# shield.net
KiCad netlist of a schematic drawn in EAGLE
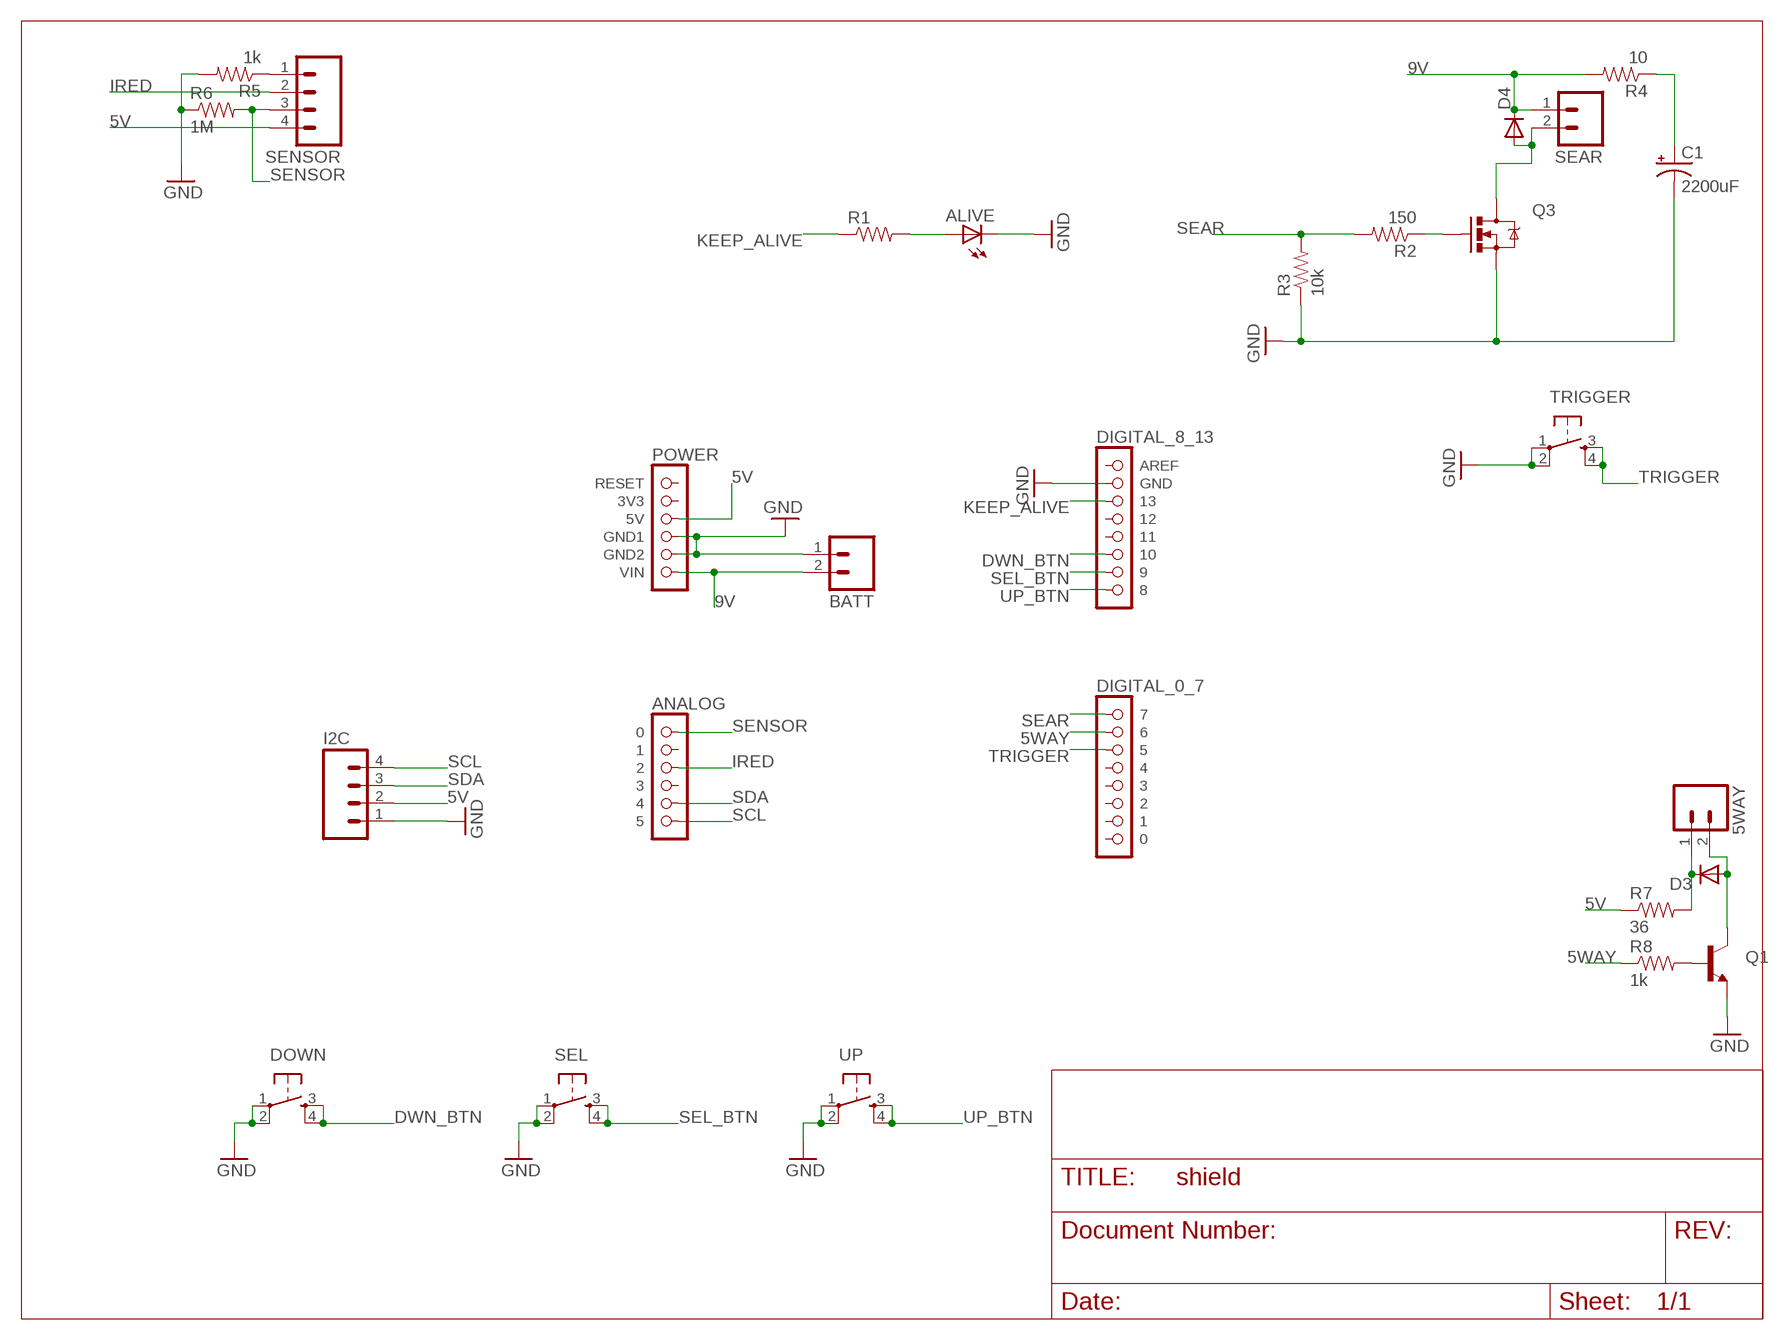
[diagram p0: schematic, sheet 1]

(export (version "E")
  (design (tool "Eeschema 10.0.6"))
  (components
    (comp (ref "5WAY")
      (value "M02PTH")
      (footprint "eagle-import:1X02")
      (libsource (lib "eagle-import") (part "M02PTH"))
    )
    (comp (ref "ALIVE")
      (value "LED3MM")
      (footprint "eagle-import:LED3MM")
      (libsource (lib "eagle-import") (part "LED3MM"))
    )
    (comp (ref "BATT")
      (value "M02PTH")
      (footprint "eagle-import:1X02")
      (libsource (lib "eagle-import") (part "M02PTH"))
    )
    (comp (ref "C1")
      (value "2200uF")
      (footprint "eagle-import:CPOL-RADIAL-1000UF-25V")
      (libsource (lib "eagle-import") (part "CAP_POLPTH4"))
    )
    (comp (ref "D3")
      (value "DIODEPTH")
      (footprint "eagle-import:DIODE-1N4001")
      (libsource (lib "eagle-import") (part "DIODEPTH"))
    )
    (comp (ref "D4")
      (value "DIODEPTH")
      (footprint "eagle-import:DIODE-1N4001")
      (libsource (lib "eagle-import") (part "DIODEPTH"))
    )
    (comp (ref "DOWN")
      (value "TAC_SWITCHPTH")
      (footprint "eagle-import:TACTILE-PTH")
      (libsource (lib "eagle-import") (part "TAC_SWITCHPTH"))
    )
    (comp (ref "I2C")
      (value "M04PTH")
      (footprint "eagle-import:1X04")
      (libsource (lib "eagle-import") (part "M04PTH"))
    )
    (comp (ref "Q1")
      (value "TRANSISTOR_NPNTO-92-AMMO")
      (footprint "eagle-import:TO-92-AMMO")
      (libsource (lib "eagle-import") (part "TRANSISTOR_NPNTO-92-AMMO"))
    )
    (comp (ref "Q3")
      (value "MOSFET-NCHANNELPTH2")
      (footprint "eagle-import:TO220V")
      (libsource (lib "eagle-import") (part "MOSFET-NCHANNELPTH2"))
    )
    (comp (ref "R1")
      (value "RESISTORPTH-1/4W")
      (footprint "eagle-import:AXIAL-0.4")
      (libsource (lib "eagle-import") (part "RESISTORPTH-1/4W"))
    )
    (comp (ref "R2")
      (value "150")
      (footprint "eagle-import:AXIAL-0.4")
      (libsource (lib "eagle-import") (part "RESISTORPTH-1/4W"))
    )
    (comp (ref "R3")
      (value "10k")
      (footprint "eagle-import:AXIAL-0.4")
      (libsource (lib "eagle-import") (part "RESISTORPTH-1/4W"))
    )
    (comp (ref "R4")
      (value "10")
      (footprint "eagle-import:AXIAL-0.4")
      (libsource (lib "eagle-import") (part "RESISTORPTH-1/4W"))
    )
    (comp (ref "R5")
      (value "1k")
      (footprint "eagle-import:AXIAL-0.4")
      (libsource (lib "eagle-import") (part "RESISTORPTH-1/4W"))
    )
    (comp (ref "R6")
      (value "1M")
      (footprint "eagle-import:AXIAL-0.4")
      (libsource (lib "eagle-import") (part "RESISTORPTH-1/4W"))
    )
    (comp (ref "R7")
      (value "36")
      (footprint "eagle-import:AXIAL-0.4")
      (libsource (lib "eagle-import") (part "RESISTORPTH-1/4W"))
    )
    (comp (ref "R8")
      (value "1k")
      (footprint "eagle-import:AXIAL-0.4")
      (libsource (lib "eagle-import") (part "RESISTORPTH-1/4W"))
    )
    (comp (ref "SEAR")
      (value "M02PTH")
      (footprint "eagle-import:1X02")
      (libsource (lib "eagle-import") (part "M02PTH"))
    )
    (comp (ref "SEL")
      (value "TAC_SWITCHPTH")
      (footprint "eagle-import:TACTILE-PTH")
      (libsource (lib "eagle-import") (part "TAC_SWITCHPTH"))
    )
    (comp (ref "SENSOR")
      (value "M04PTH")
      (footprint "eagle-import:1X04")
      (libsource (lib "eagle-import") (part "M04PTH"))
    )
    (comp (ref "TRIGGER")
      (value "TAC_SWITCHPTH")
      (footprint "eagle-import:TACTILE-PTH")
      (libsource (lib "eagle-import") (part "TAC_SWITCHPTH"))
    )
    (comp (ref "U$1")
      (value "POWER")
      (footprint "eagle-import:1X06")
      (libsource (lib "eagle-import") (part "POWER"))
    )
    (comp (ref "U$2")
      (value "ANALOG")
      (footprint "eagle-import:1X06")
      (libsource (lib "eagle-import") (part "ANALOG"))
    )
    (comp (ref "U$3")
      (value "DIGITAL_0_7")
      (footprint "eagle-import:1X08")
      (libsource (lib "eagle-import") (part "DIGITAL_0_7"))
    )
    (comp (ref "U$4")
      (value "DIGITAL_8_13")
      (footprint "eagle-import:1X08")
      (libsource (lib "eagle-import") (part "DIGITAL_8_13"))
    )
    (comp (ref "UP")
      (value "TAC_SWITCHPTH")
      (footprint "eagle-import:TACTILE-PTH")
      (libsource (lib "eagle-import") (part "TAC_SWITCHPTH"))
    )
  )
  (nets
    (net (code "1") (name "/5V") (class "Default")
      (node (ref "I2C") (pin "2") (pinfunction "2_2") (pintype "passive"))
      (node (ref "R7") (pin "P$1") (pinfunction "1_P$1") (pintype "passive"))
      (node (ref "SENSOR") (pin "4") (pinfunction "4_4") (pintype "passive"))
      (node (ref "U$1") (pin "3") (pinfunction "5V_3") (pintype "passive"))
    )
    (net (code "2") (name "/5WAY") (class "Default")
      (node (ref "R8") (pin "P$1") (pinfunction "1_P$1") (pintype "passive"))
      (node (ref "U$3") (pin "2") (pinfunction "6_2") (pintype "passive"))
    )
    (net (code "3") (name "/9V") (class "Default")
      (node (ref "BATT") (pin "2") (pinfunction "2_2") (pintype "passive"))
      (node (ref "D4") (pin "C") (pinfunction "C_C") (pintype "passive"))
      (node (ref "R4") (pin "P$2") (pinfunction "2_P$2") (pintype "passive"))
      (node (ref "SEAR") (pin "1") (pinfunction "1_1") (pintype "passive"))
      (node (ref "U$1") (pin "6") (pinfunction "VIN_6") (pintype "passive"))
    )
    (net (code "4") (name "/DWN_BTN") (class "Default")
      (node (ref "DOWN") (pin "3") (pinfunction "3_3") (pintype "passive"))
      (node (ref "DOWN") (pin "4") (pinfunction "4_4") (pintype "passive"))
      (node (ref "U$4") (pin "6") (pinfunction "10_6") (pintype "passive"))
    )
    (net (code "5") (name "/IRED") (class "Default")
      (node (ref "SENSOR") (pin "2") (pinfunction "2_2") (pintype "passive"))
      (node (ref "U$2") (pin "3") (pinfunction "2_3") (pintype "passive"))
    )
    (net (code "6") (name "/KEEP_ALIVE") (class "Default")
      (node (ref "R1") (pin "P$1") (pinfunction "1_P$1") (pintype "passive"))
      (node (ref "U$4") (pin "3") (pinfunction "13_3") (pintype "passive"))
    )
    (net (code "7") (name "/SCL") (class "Default")
      (node (ref "I2C") (pin "4") (pinfunction "4_4") (pintype "passive"))
      (node (ref "U$2") (pin "6") (pinfunction "5_6") (pintype "passive"))
    )
    (net (code "8") (name "/SDA") (class "Default")
      (node (ref "I2C") (pin "3") (pinfunction "3_3") (pintype "passive"))
      (node (ref "U$2") (pin "5") (pinfunction "4_5") (pintype "passive"))
    )
    (net (code "9") (name "/SEAR") (class "Default")
      (node (ref "R2") (pin "P$2") (pinfunction "2_P$2") (pintype "passive"))
      (node (ref "R3") (pin "P$2") (pinfunction "2_P$2") (pintype "passive"))
      (node (ref "U$3") (pin "1") (pinfunction "7_1") (pintype "passive"))
    )
    (net (code "10") (name "/SEL_BTN") (class "Default")
      (node (ref "SEL") (pin "3") (pinfunction "3_3") (pintype "passive"))
      (node (ref "SEL") (pin "4") (pinfunction "4_4") (pintype "passive"))
      (node (ref "U$4") (pin "7") (pinfunction "9_7") (pintype "passive"))
    )
    (net (code "11") (name "/SENSOR") (class "Default")
      (node (ref "R6") (pin "P$2") (pinfunction "2_P$2") (pintype "passive"))
      (node (ref "SENSOR") (pin "3") (pinfunction "3_3") (pintype "passive"))
      (node (ref "U$2") (pin "1") (pinfunction "0_1") (pintype "passive"))
    )
    (net (code "12") (name "/TRIGGER") (class "Default")
      (node (ref "TRIGGER") (pin "3") (pinfunction "3_3") (pintype "passive"))
      (node (ref "TRIGGER") (pin "4") (pinfunction "4_4") (pintype "passive"))
      (node (ref "U$3") (pin "3") (pinfunction "5_3") (pintype "passive"))
    )
    (net (code "13") (name "/UP_BTN") (class "Default")
      (node (ref "U$4") (pin "8") (pinfunction "8_8") (pintype "passive"))
      (node (ref "UP") (pin "3") (pinfunction "3_3") (pintype "passive"))
      (node (ref "UP") (pin "4") (pinfunction "4_4") (pintype "passive"))
    )
    (net (code "14") (name "GND") (class "Default")
      (node (ref "ALIVE") (pin "K") (pinfunction "C_K") (pintype "passive"))
      (node (ref "BATT") (pin "1") (pinfunction "1_1") (pintype "passive"))
      (node (ref "C1") (pin "2") (pinfunction "-_2") (pintype "passive"))
      (node (ref "DOWN") (pin "1") (pinfunction "1_1") (pintype "passive"))
      (node (ref "DOWN") (pin "2") (pinfunction "2_2") (pintype "passive"))
      (node (ref "I2C") (pin "1") (pinfunction "1_1") (pintype "passive"))
      (node (ref "Q1") (pin "1") (pinfunction "E_1") (pintype "passive"))
      (node (ref "Q3") (pin "3") (pinfunction "S_3") (pintype "passive"))
      (node (ref "R3") (pin "P$1") (pinfunction "1_P$1") (pintype "passive"))
      (node (ref "R5") (pin "P$2") (pinfunction "2_P$2") (pintype "passive"))
      (node (ref "R6") (pin "P$1") (pinfunction "1_P$1") (pintype "passive"))
      (node (ref "SEL") (pin "1") (pinfunction "1_1") (pintype "passive"))
      (node (ref "SEL") (pin "2") (pinfunction "2_2") (pintype "passive"))
      (node (ref "TRIGGER") (pin "1") (pinfunction "1_1") (pintype "passive"))
      (node (ref "TRIGGER") (pin "2") (pinfunction "2_2") (pintype "passive"))
      (node (ref "U$1") (pin "4") (pinfunction "GND1_4") (pintype "passive"))
      (node (ref "U$1") (pin "5") (pinfunction "GND2_5") (pintype "passive"))
      (node (ref "U$4") (pin "2") (pinfunction "GND_2") (pintype "passive"))
      (node (ref "UP") (pin "1") (pinfunction "1_1") (pintype "passive"))
      (node (ref "UP") (pin "2") (pinfunction "2_2") (pintype "passive"))
    )
    (net (code "15") (name "Net-(C1-+)") (class "Default")
      (node (ref "C1") (pin "1") (pinfunction "+_1") (pintype "passive"))
      (node (ref "R4") (pin "P$1") (pinfunction "1_P$1") (pintype "passive"))
    )
    (net (code "16") (name "Net-(Q1-B)") (class "Default")
      (node (ref "Q1") (pin "2") (pinfunction "B_2") (pintype "passive"))
      (node (ref "R8") (pin "P$2") (pinfunction "2_P$2") (pintype "passive"))
    )
    (net (code "17") (name "Net-(Q1-C)") (class "Default")
      (node (ref "5WAY") (pin "2") (pinfunction "2_2") (pintype "passive"))
      (node (ref "D3") (pin "A") (pinfunction "A_A") (pintype "passive"))
      (node (ref "Q1") (pin "3") (pinfunction "C_3") (pintype "passive"))
    )
    (net (code "18") (name "Net-(Q3-D)") (class "Default")
      (node (ref "D4") (pin "A") (pinfunction "A_A") (pintype "passive"))
      (node (ref "Q3") (pin "2") (pinfunction "D_2") (pintype "passive"))
      (node (ref "SEAR") (pin "2") (pinfunction "2_2") (pintype "passive"))
    )
    (net (code "19") (name "Net-(Q3-G)") (class "Default")
      (node (ref "Q3") (pin "1") (pinfunction "G_1") (pintype "passive"))
      (node (ref "R2") (pin "P$1") (pinfunction "1_P$1") (pintype "passive"))
    )
    (net (code "20") (name "Net-(R1-2)") (class "Default")
      (node (ref "ALIVE") (pin "A") (pinfunction "A_A") (pintype "passive"))
      (node (ref "R1") (pin "P$2") (pinfunction "2_P$2") (pintype "passive"))
    )
    (net (code "21") (name "Net-(R5-1)") (class "Default")
      (node (ref "R5") (pin "P$1") (pinfunction "1_P$1") (pintype "passive"))
      (node (ref "SENSOR") (pin "1") (pinfunction "1_1") (pintype "passive"))
    )
    (net (code "22") (name "Net-(R7-2)") (class "Default")
      (node (ref "5WAY") (pin "1") (pinfunction "1_1") (pintype "passive"))
      (node (ref "D3") (pin "C") (pinfunction "C_C") (pintype "passive"))
      (node (ref "R7") (pin "P$2") (pinfunction "2_P$2") (pintype "passive"))
    )
    (net (code "23") (name "unconnected-(U$1-3V3-Pad2)") (class "Default")
      (node (ref "U$1") (pin "2") (pinfunction "3V3_2") (pintype "passive"))
    )
    (net (code "24") (name "unconnected-(U$1-RESET-Pad1)") (class "Default")
      (node (ref "U$1") (pin "1") (pinfunction "RESET_1") (pintype "passive"))
    )
    (net (code "25") (name "unconnected-(U$2-1-Pad2)") (class "Default")
      (node (ref "U$2") (pin "2") (pinfunction "1_2") (pintype "passive"))
    )
    (net (code "26") (name "unconnected-(U$2-3-Pad4)") (class "Default")
      (node (ref "U$2") (pin "4") (pinfunction "3_4") (pintype "passive"))
    )
    (net (code "27") (name "unconnected-(U$3-0-Pad8)") (class "Default")
      (node (ref "U$3") (pin "8") (pinfunction "0_8") (pintype "passive"))
    )
    (net (code "28") (name "unconnected-(U$3-1-Pad7)") (class "Default")
      (node (ref "U$3") (pin "7") (pinfunction "1_7") (pintype "passive"))
    )
    (net (code "29") (name "unconnected-(U$3-2-Pad6)") (class "Default")
      (node (ref "U$3") (pin "6") (pinfunction "2_6") (pintype "passive"))
    )
    (net (code "30") (name "unconnected-(U$3-3-Pad5)") (class "Default")
      (node (ref "U$3") (pin "5") (pinfunction "3_5") (pintype "passive"))
    )
    (net (code "31") (name "unconnected-(U$3-Pad4)") (class "Default")
      (node (ref "U$3") (pin "4") (pinfunction "4_4") (pintype "passive"))
    )
    (net (code "32") (name "unconnected-(U$4-11-Pad5)") (class "Default")
      (node (ref "U$4") (pin "5") (pinfunction "11_5") (pintype "passive"))
    )
    (net (code "33") (name "unconnected-(U$4-12-Pad4)") (class "Default")
      (node (ref "U$4") (pin "4") (pinfunction "12_4") (pintype "passive"))
    )
    (net (code "34") (name "unconnected-(U$4-AREF-Pad1)") (class "Default")
      (node (ref "U$4") (pin "1") (pinfunction "AREF_1") (pintype "passive"))
    )
  )
)
